# 4channelsRelay.net
KiCad netlist of a schematic drawn in EAGLE
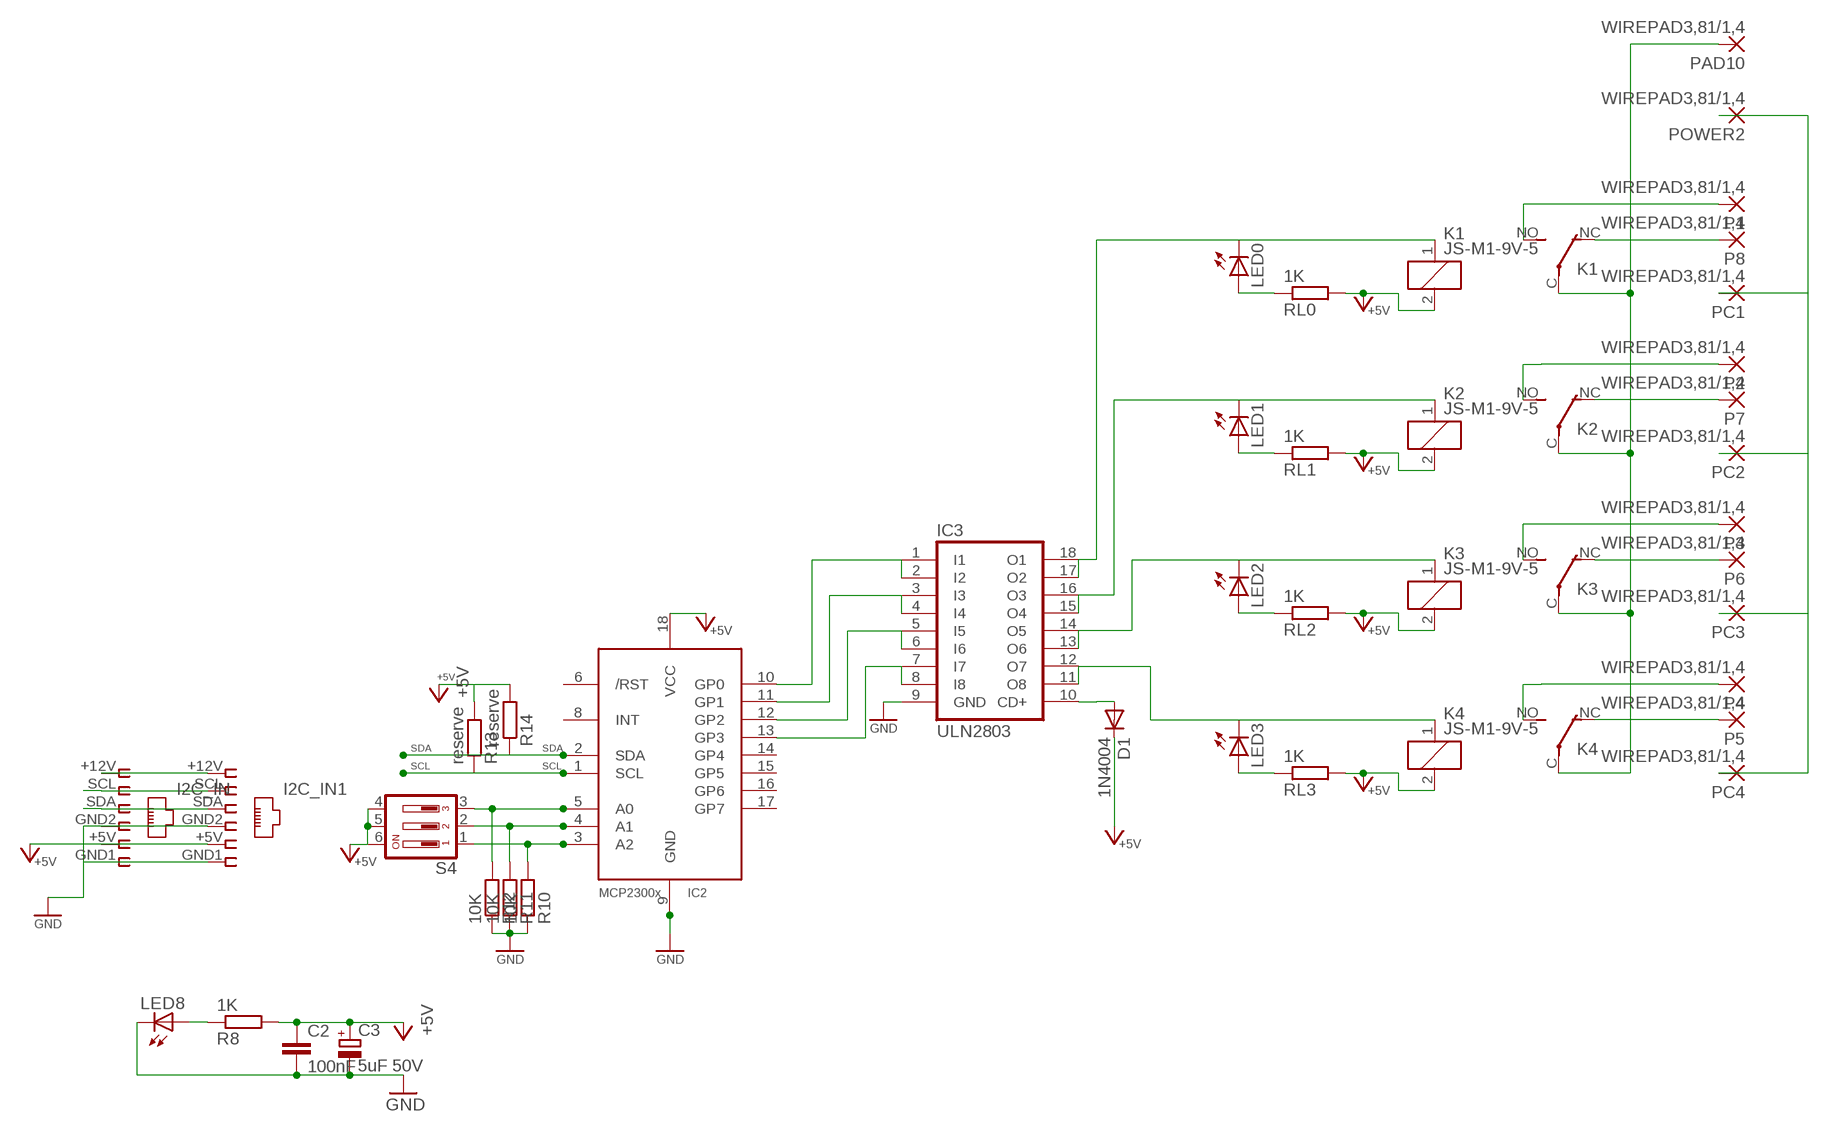
[diagram p0: schematic, sheet 1]

(export (version "E")
  (design (tool "Eeschema 10.0.6"))
  (components
    (comp (ref "C2")
      (value "100nF")
      (footprint "eagle-import:C1206")
      (libsource (lib "eagle-import") (part "C-EUC1206"))
    )
    (comp (ref "C3")
      (value "5uF 50V")
      (footprint "eagle-import:E3,5-8")
      (libsource (lib "eagle-import") (part "CPOL-EUE3.5-8"))
    )
    (comp (ref "D1")
      (value "1N4004")
      (footprint "eagle-import:DO41-10")
      (libsource (lib "eagle-import") (part "1N4004"))
    )
    (comp (ref "I2C_IN")
      (value "I2C 1")
      (footprint "eagle-import:RJ12-STRAIGHT-I2C")
      (libsource (lib "eagle-import") (part "RJ12STRAIGHT-I2C"))
    )
    (comp (ref "I2C_IN1")
      (value "I2C 2")
      (footprint "eagle-import:RJ12-STRAIGHT-I2C")
      (libsource (lib "eagle-import") (part "RJ12STRAIGHT-I2C"))
    )
    (comp (ref "IC2")
      (value "MCP2300X/P")
      (footprint "eagle-import:DIL18")
      (libsource (lib "eagle-import") (part "MCP2300X/P"))
    )
    (comp (ref "IC3")
      (value "ULN2803")
      (footprint "eagle-import:DIL18")
      (libsource (lib "eagle-import") (part "ULN2803A"))
    )
    (comp (ref "K1")
      (value "JS-M1-9V-5")
      (footprint "eagle-import:JS-M")
      (libsource (lib "eagle-import") (part "JS-M1-9V-5"))
    )
    (comp (ref "K2")
      (value "JS-M1-9V-5")
      (footprint "eagle-import:JS-M")
      (libsource (lib "eagle-import") (part "JS-M1-9V-5"))
    )
    (comp (ref "K3")
      (value "JS-M1-9V-5")
      (footprint "eagle-import:JS-M")
      (libsource (lib "eagle-import") (part "JS-M1-9V-5"))
    )
    (comp (ref "K4")
      (value "JS-M1-9V-5")
      (footprint "eagle-import:JS-M")
      (libsource (lib "eagle-import") (part "JS-M1-9V-5"))
    )
    (comp (ref "LED0")
      (value "LED3MM")
      (footprint "eagle-import:LED3MM")
      (libsource (lib "eagle-import") (part "LED3MM"))
    )
    (comp (ref "LED1")
      (value "LED3MM")
      (footprint "eagle-import:LED3MM")
      (libsource (lib "eagle-import") (part "LED3MM"))
    )
    (comp (ref "LED2")
      (value "LED3MM")
      (footprint "eagle-import:LED3MM")
      (libsource (lib "eagle-import") (part "LED3MM"))
    )
    (comp (ref "LED3")
      (value "LED3MM")
      (footprint "eagle-import:LED3MM")
      (libsource (lib "eagle-import") (part "LED3MM"))
    )
    (comp (ref "LED8")
      (value "LED3MM")
      (footprint "eagle-import:LED3MM")
      (libsource (lib "eagle-import") (part "LED3MM"))
    )
    (comp (ref "P1")
      (value "WIREPAD3,81/1,4")
      (footprint "eagle-import:3,81_1,4")
      (libsource (lib "eagle-import") (part "WIREPAD3,81/1,4"))
    )
    (comp (ref "P2")
      (value "WIREPAD3,81/1,4")
      (footprint "eagle-import:3,81_1,4")
      (libsource (lib "eagle-import") (part "WIREPAD3,81/1,4"))
    )
    (comp (ref "P3")
      (value "WIREPAD3,81/1,4")
      (footprint "eagle-import:3,81_1,4")
      (libsource (lib "eagle-import") (part "WIREPAD3,81/1,4"))
    )
    (comp (ref "P4")
      (value "WIREPAD3,81/1,4")
      (footprint "eagle-import:3,81_1,4")
      (libsource (lib "eagle-import") (part "WIREPAD3,81/1,4"))
    )
    (comp (ref "P5")
      (value "WIREPAD3,81/1,4")
      (footprint "eagle-import:3,81_1,4")
      (libsource (lib "eagle-import") (part "WIREPAD3,81/1,4"))
    )
    (comp (ref "P6")
      (value "WIREPAD3,81/1,4")
      (footprint "eagle-import:3,81_1,4")
      (libsource (lib "eagle-import") (part "WIREPAD3,81/1,4"))
    )
    (comp (ref "P7")
      (value "WIREPAD3,81/1,4")
      (footprint "eagle-import:3,81_1,4")
      (libsource (lib "eagle-import") (part "WIREPAD3,81/1,4"))
    )
    (comp (ref "P8")
      (value "WIREPAD3,81/1,4")
      (footprint "eagle-import:3,81_1,4")
      (libsource (lib "eagle-import") (part "WIREPAD3,81/1,4"))
    )
    (comp (ref "PAD10")
      (value "WIREPAD3,81/1,4")
      (footprint "eagle-import:3,81_1,4")
      (libsource (lib "eagle-import") (part "WIREPAD3,81/1,4"))
    )
    (comp (ref "PC1")
      (value "WIREPAD3,81/1,4")
      (footprint "eagle-import:3,81_1,4")
      (libsource (lib "eagle-import") (part "WIREPAD3,81/1,4"))
    )
    (comp (ref "PC2")
      (value "WIREPAD3,81/1,4")
      (footprint "eagle-import:3,81_1,4")
      (libsource (lib "eagle-import") (part "WIREPAD3,81/1,4"))
    )
    (comp (ref "PC3")
      (value "WIREPAD3,81/1,4")
      (footprint "eagle-import:3,81_1,4")
      (libsource (lib "eagle-import") (part "WIREPAD3,81/1,4"))
    )
    (comp (ref "PC4")
      (value "WIREPAD3,81/1,4")
      (footprint "eagle-import:3,81_1,4")
      (libsource (lib "eagle-import") (part "WIREPAD3,81/1,4"))
    )
    (comp (ref "POWER2")
      (value "WIREPAD3,81/1,4")
      (footprint "eagle-import:3,81_1,4")
      (libsource (lib "eagle-import") (part "WIREPAD3,81/1,4"))
    )
    (comp (ref "R8")
      (value "1K")
      (footprint "eagle-import:M1206")
      (libsource (lib "eagle-import") (part "R-EU_M1206"))
    )
    (comp (ref "R10")
      (value "10K")
      (footprint "eagle-import:M1206")
      (libsource (lib "eagle-import") (part "R-EU_M1206"))
    )
    (comp (ref "R11")
      (value "10K")
      (footprint "eagle-import:M1206")
      (libsource (lib "eagle-import") (part "R-EU_M1206"))
    )
    (comp (ref "R12")
      (value "10K")
      (footprint "eagle-import:M1206")
      (libsource (lib "eagle-import") (part "R-EU_M1206"))
    )
    (comp (ref "R13")
      (value "reserve")
      (footprint "eagle-import:M1206")
      (libsource (lib "eagle-import") (part "R-EU_M1206"))
    )
    (comp (ref "R14")
      (value "reserve")
      (footprint "eagle-import:M1206")
      (libsource (lib "eagle-import") (part "R-EU_M1206"))
    )
    (comp (ref "RL0")
      (value "1K")
      (footprint "eagle-import:M1206")
      (libsource (lib "eagle-import") (part "R-EU_M1206"))
    )
    (comp (ref "RL1")
      (value "1K")
      (footprint "eagle-import:M1206")
      (libsource (lib "eagle-import") (part "R-EU_M1206"))
    )
    (comp (ref "RL2")
      (value "1K")
      (footprint "eagle-import:M1206")
      (libsource (lib "eagle-import") (part "R-EU_M1206"))
    )
    (comp (ref "RL3")
      (value "1K")
      (footprint "eagle-import:M1206")
      (libsource (lib "eagle-import") (part "R-EU_M1206"))
    )
    (comp (ref "S4")
      (value "DIP03YL")
      (footprint "eagle-import:DIP03YL")
      (libsource (lib "eagle-import") (part "DIP03YL"))
    )
  )
  (nets
    (net (code "1") (name "+5V") (class "Default")
      (node (ref "C2") (pin "1") (pinfunction "1_1") (pintype "passive"))
      (node (ref "C3") (pin "+") (pinfunction "+_+") (pintype "passive"))
      (node (ref "D1") (pin "C") (pinfunction "C_C") (pintype "passive"))
      (node (ref "I2C_IN") (pin "+5V") (pinfunction "5_+5V") (pintype "power_in"))
      (node (ref "I2C_IN1") (pin "+5V") (pinfunction "5_+5V") (pintype "power_in"))
      (node (ref "IC2") (pin "18") (pinfunction "VCC_18") (pintype "power_in"))
      (node (ref "K1") (pin "2") (pinfunction "2_2") (pintype "passive"))
      (node (ref "K2") (pin "2") (pinfunction "2_2") (pintype "passive"))
      (node (ref "K3") (pin "2") (pinfunction "2_2") (pintype "passive"))
      (node (ref "K4") (pin "2") (pinfunction "2_2") (pintype "passive"))
      (node (ref "R13") (pin "2") (pinfunction "2_2") (pintype "passive"))
      (node (ref "R14") (pin "2") (pinfunction "2_2") (pintype "passive"))
      (node (ref "R8") (pin "2") (pinfunction "2_2") (pintype "passive"))
      (node (ref "RL0") (pin "2") (pinfunction "2_2") (pintype "passive"))
      (node (ref "RL1") (pin "2") (pinfunction "2_2") (pintype "passive"))
      (node (ref "RL2") (pin "2") (pinfunction "2_2") (pintype "passive"))
      (node (ref "RL3") (pin "2") (pinfunction "2_2") (pintype "passive"))
      (node (ref "S4") (pin "4") (pinfunction "4_4") (pintype "passive"))
      (node (ref "S4") (pin "5") (pinfunction "5_5") (pintype "passive"))
      (node (ref "S4") (pin "6") (pinfunction "6_6") (pintype "passive"))
    )
    (net (code "2") (name "/SCL") (class "Default")
      (node (ref "I2C_IN") (pin "SCL") (pinfunction "2_SCL") (pintype "bidirectional"))
      (node (ref "I2C_IN1") (pin "SCL") (pinfunction "2_SCL") (pintype "bidirectional"))
      (node (ref "IC2") (pin "1") (pinfunction "SCL_1") (pintype "bidirectional"))
      (node (ref "R13") (pin "1") (pinfunction "1_1") (pintype "passive"))
    )
    (net (code "3") (name "/SDA") (class "Default")
      (node (ref "I2C_IN") (pin "SDA") (pinfunction "3_SDA") (pintype "bidirectional"))
      (node (ref "I2C_IN1") (pin "SDA") (pinfunction "3_SDA") (pintype "bidirectional"))
      (node (ref "IC2") (pin "2") (pinfunction "SDA_2") (pintype "bidirectional"))
      (node (ref "R14") (pin "1") (pinfunction "1_1") (pintype "passive"))
    )
    (net (code "4") (name "GND") (class "Default")
      (node (ref "C2") (pin "2") (pinfunction "2_2") (pintype "passive"))
      (node (ref "C3") (pin "-") (pinfunction "-_-") (pintype "passive"))
      (node (ref "I2C_IN") (pin "GND1") (pinfunction "6_GND1") (pintype "power_in"))
      (node (ref "I2C_IN") (pin "GND2") (pinfunction "4_GND2") (pintype "power_in"))
      (node (ref "I2C_IN1") (pin "GND1") (pinfunction "6_GND1") (pintype "power_in"))
      (node (ref "I2C_IN1") (pin "GND2") (pinfunction "4_GND2") (pintype "power_in"))
      (node (ref "IC2") (pin "9") (pinfunction "GND_9") (pintype "power_in"))
      (node (ref "IC3") (pin "9") (pinfunction "GND_9") (pintype "power_in"))
      (node (ref "LED8") (pin "K") (pinfunction "C_K") (pintype "passive"))
      (node (ref "R10") (pin "1") (pinfunction "1_1") (pintype "passive"))
      (node (ref "R11") (pin "1") (pinfunction "1_1") (pintype "passive"))
      (node (ref "R12") (pin "1") (pinfunction "1_1") (pintype "passive"))
    )
    (net (code "5") (name "Net-(I2C_IN-1)") (class "Default")
      (node (ref "I2C_IN") (pin "+12V") (pinfunction "1_+12V") (pintype "power_in"))
      (node (ref "I2C_IN1") (pin "+12V") (pinfunction "1_+12V") (pintype "power_in"))
    )
    (net (code "6") (name "Net-(IC2-A0)") (class "Default")
      (node (ref "IC2") (pin "5") (pinfunction "A0_5") (pintype "input"))
      (node (ref "R12") (pin "2") (pinfunction "2_2") (pintype "passive"))
      (node (ref "S4") (pin "3") (pinfunction "3_3") (pintype "passive"))
    )
    (net (code "7") (name "Net-(IC2-A1)") (class "Default")
      (node (ref "IC2") (pin "4") (pinfunction "A1_4") (pintype "input"))
      (node (ref "R11") (pin "2") (pinfunction "2_2") (pintype "passive"))
      (node (ref "S4") (pin "2") (pinfunction "2_2") (pintype "passive"))
    )
    (net (code "8") (name "Net-(IC2-A2)") (class "Default")
      (node (ref "IC2") (pin "3") (pinfunction "A2_3") (pintype "input"))
      (node (ref "R10") (pin "2") (pinfunction "2_2") (pintype "passive"))
      (node (ref "S4") (pin "1") (pinfunction "1_1") (pintype "passive"))
    )
    (net (code "9") (name "Net-(IC2-GP0)") (class "Default")
      (node (ref "IC2") (pin "10") (pinfunction "GP0_10") (pintype "bidirectional"))
      (node (ref "IC3") (pin "1") (pinfunction "I1_1") (pintype "input"))
      (node (ref "IC3") (pin "2") (pinfunction "I2_2") (pintype "input"))
    )
    (net (code "10") (name "Net-(IC2-GP1)") (class "Default")
      (node (ref "IC2") (pin "11") (pinfunction "GP1_11") (pintype "bidirectional"))
      (node (ref "IC3") (pin "3") (pinfunction "I3_3") (pintype "input"))
      (node (ref "IC3") (pin "4") (pinfunction "I4_4") (pintype "input"))
    )
    (net (code "11") (name "Net-(IC2-GP2)") (class "Default")
      (node (ref "IC2") (pin "12") (pinfunction "GP2_12") (pintype "bidirectional"))
      (node (ref "IC3") (pin "5") (pinfunction "I5_5") (pintype "input"))
      (node (ref "IC3") (pin "6") (pinfunction "I6_6") (pintype "input"))
    )
    (net (code "12") (name "Net-(IC2-GP3)") (class "Default")
      (node (ref "IC2") (pin "13") (pinfunction "GP3_13") (pintype "bidirectional"))
      (node (ref "IC3") (pin "7") (pinfunction "I7_7") (pintype "input"))
      (node (ref "IC3") (pin "8") (pinfunction "I8_8") (pintype "input"))
    )
    (net (code "13") (name "Net-(IC3-CD+)") (class "Default")
      (node (ref "D1") (pin "A") (pinfunction "A_A") (pintype "passive"))
      (node (ref "IC3") (pin "10") (pinfunction "CD+_10") (pintype "passive"))
    )
    (net (code "14") (name "Net-(IC3-O1)") (class "Default")
      (node (ref "IC3") (pin "17") (pinfunction "O2_17") (pintype "open_collector"))
      (node (ref "IC3") (pin "18") (pinfunction "O1_18") (pintype "open_collector"))
      (node (ref "K1") (pin "1") (pinfunction "1_1") (pintype "passive"))
      (node (ref "LED0") (pin "K") (pinfunction "C_K") (pintype "passive"))
    )
    (net (code "15") (name "Net-(IC3-O3)") (class "Default")
      (node (ref "IC3") (pin "15") (pinfunction "O4_15") (pintype "open_collector"))
      (node (ref "IC3") (pin "16") (pinfunction "O3_16") (pintype "open_collector"))
      (node (ref "K2") (pin "1") (pinfunction "1_1") (pintype "passive"))
      (node (ref "LED1") (pin "K") (pinfunction "C_K") (pintype "passive"))
    )
    (net (code "16") (name "Net-(IC3-O5)") (class "Default")
      (node (ref "IC3") (pin "13") (pinfunction "O6_13") (pintype "open_collector"))
      (node (ref "IC3") (pin "14") (pinfunction "O5_14") (pintype "open_collector"))
      (node (ref "K3") (pin "1") (pinfunction "1_1") (pintype "passive"))
      (node (ref "LED2") (pin "K") (pinfunction "C_K") (pintype "passive"))
    )
    (net (code "17") (name "Net-(IC3-O7)") (class "Default")
      (node (ref "IC3") (pin "11") (pinfunction "O8_11") (pintype "open_collector"))
      (node (ref "IC3") (pin "12") (pinfunction "O7_12") (pintype "open_collector"))
      (node (ref "K4") (pin "1") (pinfunction "1_1") (pintype "passive"))
      (node (ref "LED3") (pin "K") (pinfunction "C_K") (pintype "passive"))
    )
    (net (code "18") (name "Net-(K1B-O)") (class "Default")
      (node (ref "K1") (pin "NC") (pinfunction "O_NC") (pintype "passive"))
      (node (ref "P8") (pin "1") (pinfunction "P_1") (pintype "passive"))
    )
    (net (code "19") (name "Net-(K1B-P)") (class "Default")
      (node (ref "K1") (pin "C") (pinfunction "P_C") (pintype "passive"))
      (node (ref "K2") (pin "C") (pinfunction "P_C") (pintype "passive"))
      (node (ref "K3") (pin "C") (pinfunction "P_C") (pintype "passive"))
      (node (ref "K4") (pin "C") (pinfunction "P_C") (pintype "passive"))
      (node (ref "PAD10") (pin "1") (pinfunction "P_1") (pintype "passive"))
    )
    (net (code "20") (name "Net-(K1B-S)") (class "Default")
      (node (ref "K1") (pin "NO") (pinfunction "S_NO") (pintype "passive"))
      (node (ref "P1") (pin "1") (pinfunction "P_1") (pintype "passive"))
    )
    (net (code "21") (name "Net-(K2B-O)") (class "Default")
      (node (ref "K2") (pin "NC") (pinfunction "O_NC") (pintype "passive"))
      (node (ref "P7") (pin "1") (pinfunction "P_1") (pintype "passive"))
    )
    (net (code "22") (name "Net-(K2B-S)") (class "Default")
      (node (ref "K2") (pin "NO") (pinfunction "S_NO") (pintype "passive"))
      (node (ref "P2") (pin "1") (pinfunction "P_1") (pintype "passive"))
    )
    (net (code "23") (name "Net-(K3B-O)") (class "Default")
      (node (ref "K3") (pin "NC") (pinfunction "O_NC") (pintype "passive"))
      (node (ref "P6") (pin "1") (pinfunction "P_1") (pintype "passive"))
    )
    (net (code "24") (name "Net-(K3B-S)") (class "Default")
      (node (ref "K3") (pin "NO") (pinfunction "S_NO") (pintype "passive"))
      (node (ref "P3") (pin "1") (pinfunction "P_1") (pintype "passive"))
    )
    (net (code "25") (name "Net-(K4B-O)") (class "Default")
      (node (ref "K4") (pin "NC") (pinfunction "O_NC") (pintype "passive"))
      (node (ref "P5") (pin "1") (pinfunction "P_1") (pintype "passive"))
    )
    (net (code "26") (name "Net-(K4B-S)") (class "Default")
      (node (ref "K4") (pin "NO") (pinfunction "S_NO") (pintype "passive"))
      (node (ref "P4") (pin "1") (pinfunction "P_1") (pintype "passive"))
    )
    (net (code "27") (name "Net-(LED0-PadA)") (class "Default")
      (node (ref "LED0") (pin "A") (pinfunction "A_A") (pintype "passive"))
      (node (ref "RL0") (pin "1") (pinfunction "1_1") (pintype "passive"))
    )
    (net (code "28") (name "Net-(LED1-PadA)") (class "Default")
      (node (ref "LED1") (pin "A") (pinfunction "A_A") (pintype "passive"))
      (node (ref "RL1") (pin "1") (pinfunction "1_1") (pintype "passive"))
    )
    (net (code "29") (name "Net-(LED2-PadA)") (class "Default")
      (node (ref "LED2") (pin "A") (pinfunction "A_A") (pintype "passive"))
      (node (ref "RL2") (pin "1") (pinfunction "1_1") (pintype "passive"))
    )
    (net (code "30") (name "Net-(LED3-PadA)") (class "Default")
      (node (ref "LED3") (pin "A") (pinfunction "A_A") (pintype "passive"))
      (node (ref "RL3") (pin "1") (pinfunction "1_1") (pintype "passive"))
    )
    (net (code "31") (name "Net-(LED8-PadA)") (class "Default")
      (node (ref "LED8") (pin "A") (pinfunction "A_A") (pintype "passive"))
      (node (ref "R8") (pin "1") (pinfunction "1_1") (pintype "passive"))
    )
    (net (code "32") (name "Net-(PC1-P)") (class "Default")
      (node (ref "PC1") (pin "1") (pinfunction "P_1") (pintype "passive"))
      (node (ref "PC2") (pin "1") (pinfunction "P_1") (pintype "passive"))
      (node (ref "PC3") (pin "1") (pinfunction "P_1") (pintype "passive"))
      (node (ref "PC4") (pin "1") (pinfunction "P_1") (pintype "passive"))
      (node (ref "POWER2") (pin "1") (pinfunction "P_1") (pintype "passive"))
    )
    (net (code "33") (name "unconnected-(IC2-GP4-Pad14)") (class "Default")
      (node (ref "IC2") (pin "14") (pinfunction "GP4_14") (pintype "bidirectional"))
    )
    (net (code "34") (name "unconnected-(IC2-GP5-Pad15)") (class "Default")
      (node (ref "IC2") (pin "15") (pinfunction "GP5_15") (pintype "bidirectional"))
    )
    (net (code "35") (name "unconnected-(IC2-GP6-Pad16)") (class "Default")
      (node (ref "IC2") (pin "16") (pinfunction "GP6_16") (pintype "bidirectional"))
    )
    (net (code "36") (name "unconnected-(IC2-GP7-Pad17)") (class "Default")
      (node (ref "IC2") (pin "17") (pinfunction "GP7_17") (pintype "bidirectional"))
    )
    (net (code "37") (name "unconnected-(IC2-INT-Pad8)") (class "Default")
      (node (ref "IC2") (pin "8") (pinfunction "INT_8") (pintype "output"))
    )
    (net (code "38") (name "unconnected-(IC2-{slash}RST-Pad6)") (class "Default")
      (node (ref "IC2") (pin "6") (pinfunction "/RST_6") (pintype "input"))
    )
  )
)
